# SCH_homework1_2025-05-14.net
KiCad netlist of a schematic drawn in EasyEDA
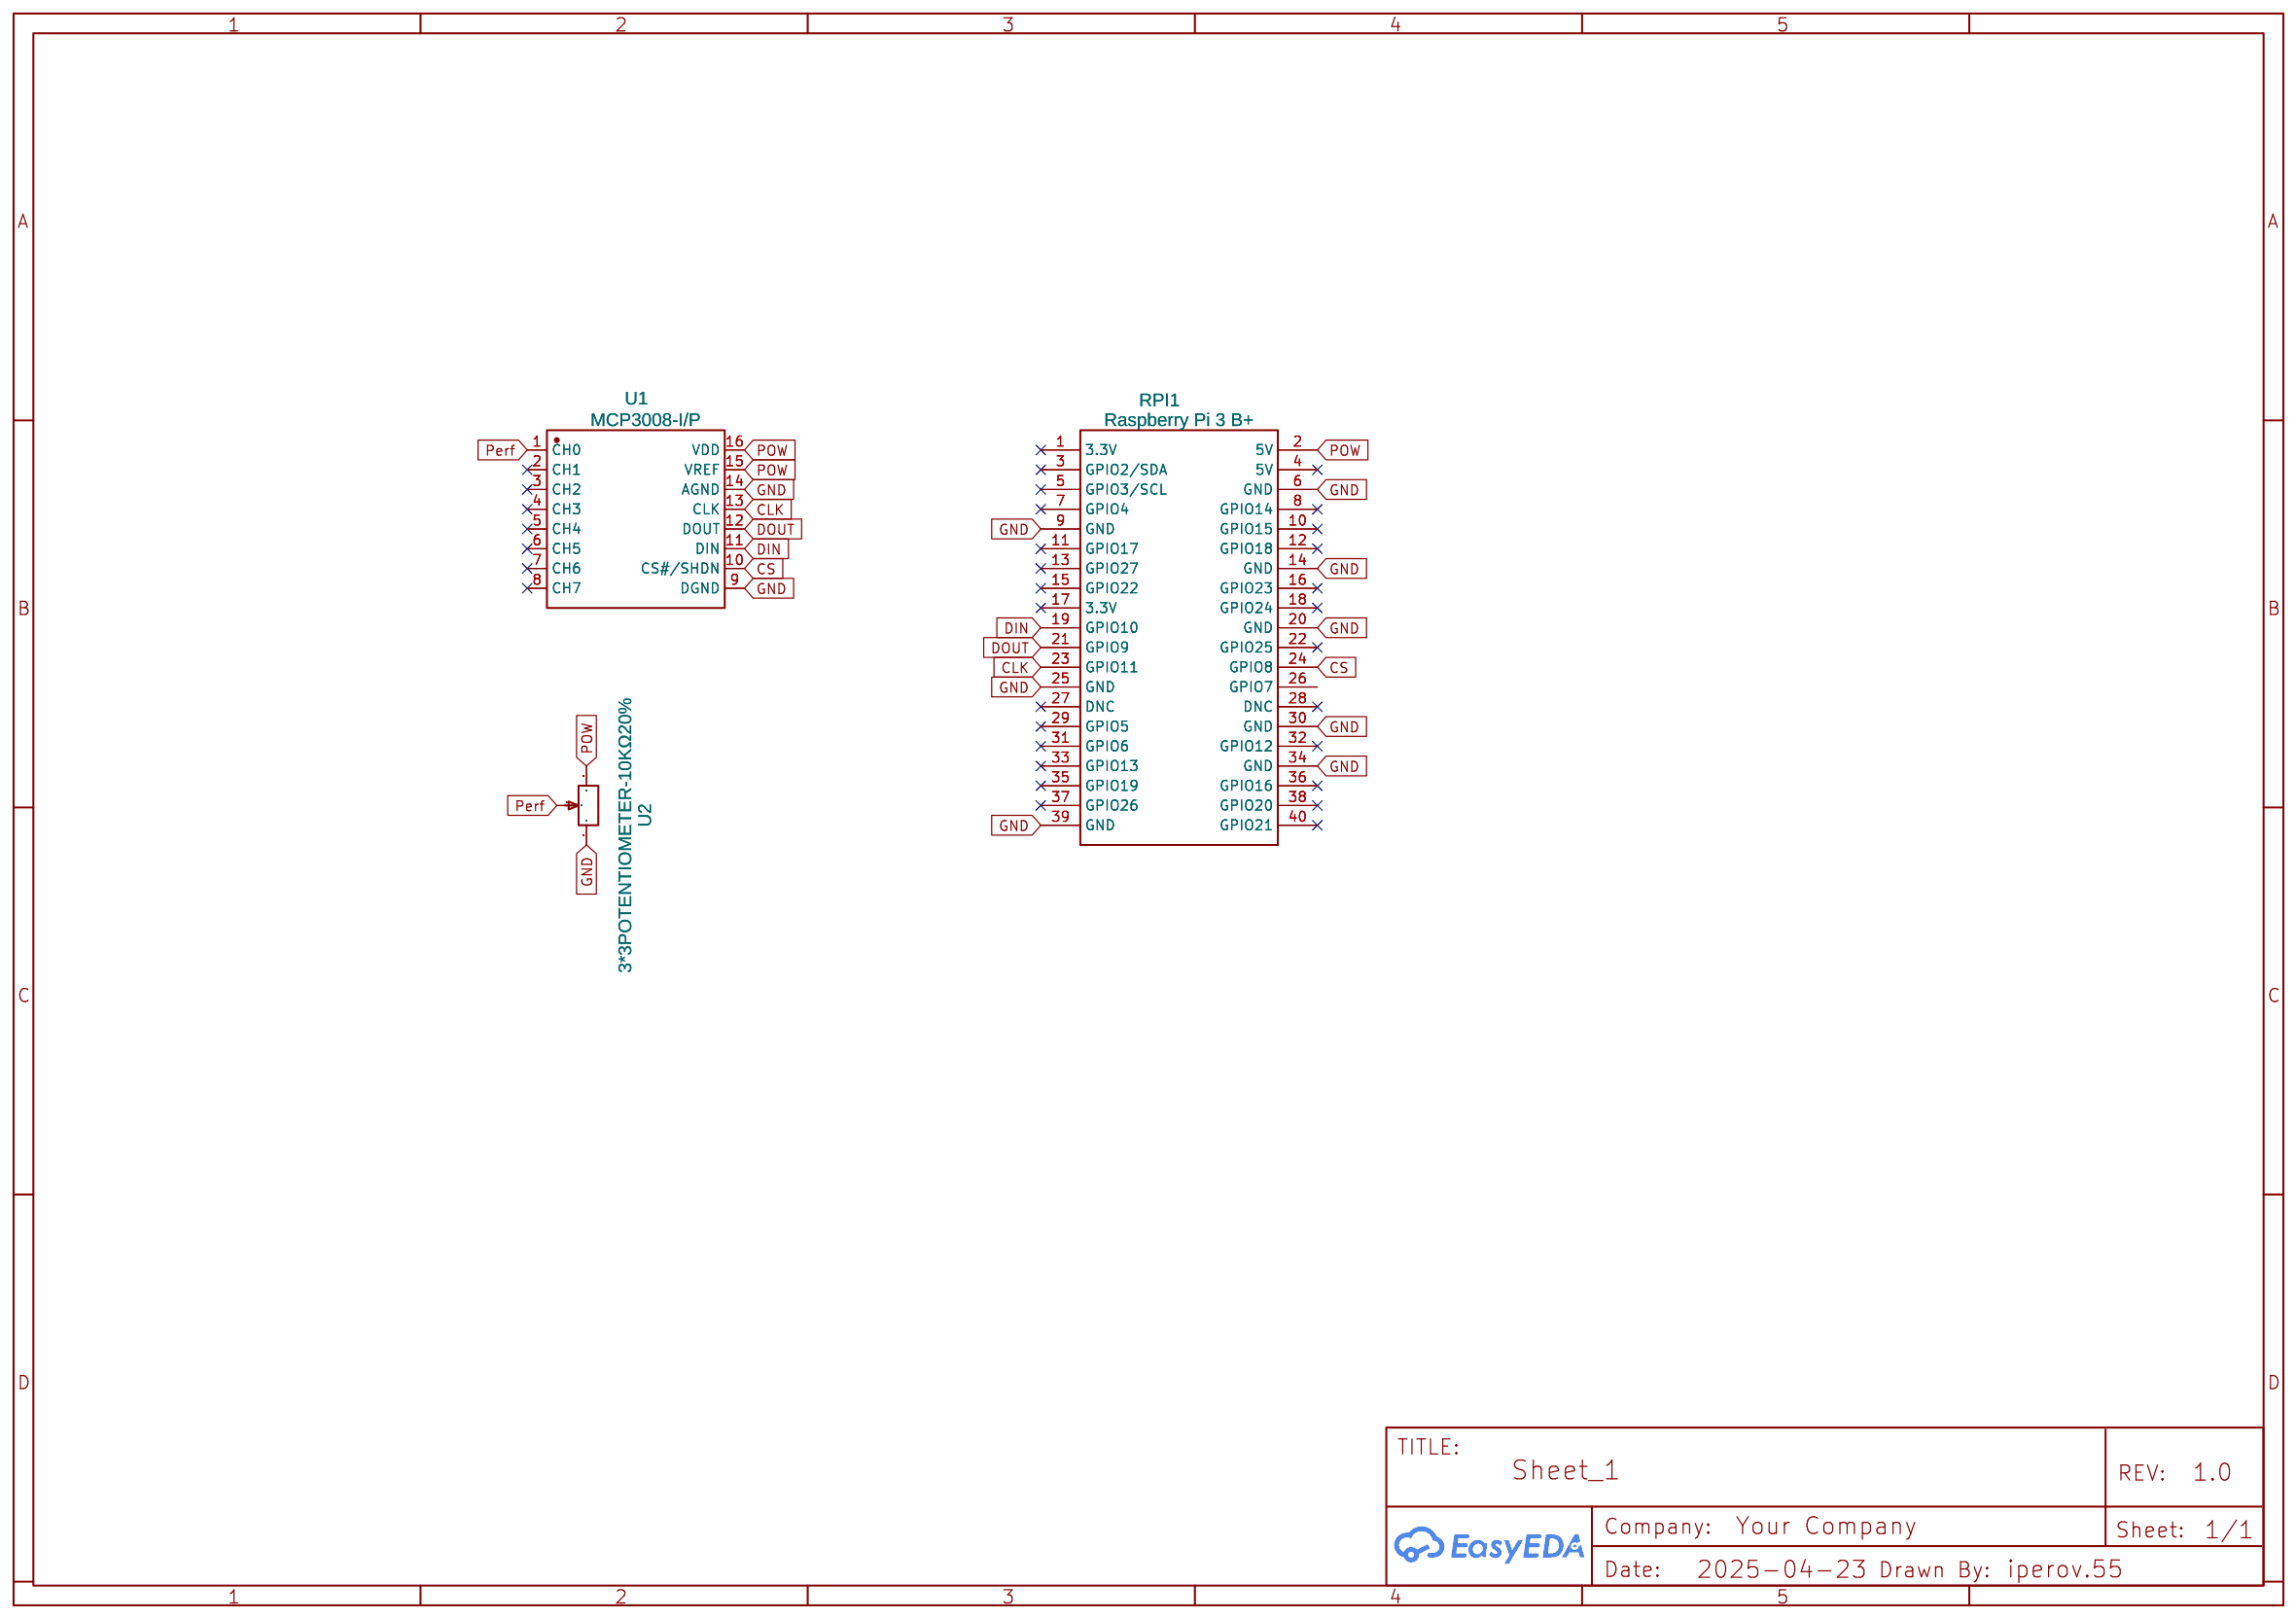
[diagram p0: schematic sheet]

(export (version "E")
  (design (tool "Eeschema 10.0.6"))
  (components
    (comp (ref "RPI1")
      (value "Raspberry Pi 3 B+")
      (fields
        (field (name "Manufacturer Part") "Raspberry Pi 3 - Model B+ - 1.4GHz Cortex-A53 with 1GB RAM")
        (field (name "Manufacturer") "Raspberry Pi")
      )
      (libsource (lib "") (part "Raspberry Pi 3 B+"))
    )
    (comp (ref "U1")
      (value "MCP3008-I/P")
      (fields (field (name "Manufacturer") "MICROCHIP(美国微芯)"))
      (libsource (lib "") (part "MCP3008-I/P"))
    )
    (comp (ref "U2")
      (value "3*3POTENTIOMETER-10KΩ20%")
      (fields (field (name "Manufacturer Part") "3*3Potentiometer-10kΩ20%"))
      (libsource (lib "") (part "3*3POTENTIOMETER-10KΩ20%"))
    )
  )
  (nets
    (net (code "1") (name "CLK") (class "Default")
      (node (ref "RPI1") (pin "23") (pinfunction "GPIO11_23") (pintype "bidirectional"))
      (node (ref "U1") (pin "13") (pinfunction "CLK_13") (pintype "unspecified"))
    )
    (net (code "2") (name "CS") (class "Default")
      (node (ref "RPI1") (pin "24") (pinfunction "GPIO8_24") (pintype "bidirectional"))
      (node (ref "U1") (pin "10") (pinfunction "CS#/SHDN_10") (pintype "unspecified"))
    )
    (net (code "3") (name "DIN") (class "Default")
      (node (ref "RPI1") (pin "19") (pinfunction "GPIO10_19") (pintype "bidirectional"))
      (node (ref "U1") (pin "11") (pinfunction "DIN_11") (pintype "unspecified"))
    )
    (net (code "4") (name "DOUT") (class "Default")
      (node (ref "RPI1") (pin "21") (pinfunction "GPIO9_21") (pintype "bidirectional"))
      (node (ref "U1") (pin "12") (pinfunction "DOUT_12") (pintype "unspecified"))
    )
    (net (code "5") (name "GND") (class "Default")
      (node (ref "RPI1") (pin "14") (pinfunction "GND_14") (pintype "unspecified"))
      (node (ref "RPI1") (pin "20") (pinfunction "GND_20") (pintype "unspecified"))
      (node (ref "RPI1") (pin "25") (pinfunction "GND_25") (pintype "unspecified"))
      (node (ref "RPI1") (pin "30") (pinfunction "GND_30") (pintype "unspecified"))
      (node (ref "RPI1") (pin "34") (pinfunction "GND_34") (pintype "unspecified"))
      (node (ref "RPI1") (pin "39") (pinfunction "GND_39") (pintype "unspecified"))
      (node (ref "RPI1") (pin "6") (pinfunction "GND_6") (pintype "unspecified"))
      (node (ref "RPI1") (pin "9") (pinfunction "GND_9") (pintype "unspecified"))
      (node (ref "U1") (pin "14") (pinfunction "AGND_14") (pintype "unspecified"))
      (node (ref "U1") (pin "9") (pinfunction "DGND_9") (pintype "unspecified"))
      (node (ref "U2") (pin "1") (pinfunction "1_1") (pintype "input"))
    )
    (net (code "6") (name "POW") (class "Default")
      (node (ref "RPI1") (pin "2") (pinfunction "5V_2") (pintype "passive"))
      (node (ref "U1") (pin "15") (pinfunction "VREF_15") (pintype "unspecified"))
      (node (ref "U1") (pin "16") (pinfunction "VDD_16") (pintype "unspecified"))
      (node (ref "U2") (pin "3") (pinfunction "3_3") (pintype "input"))
    )
    (net (code "7") (name "Perf") (class "Default")
      (node (ref "U1") (pin "1") (pinfunction "CH0_1") (pintype "unspecified"))
      (node (ref "U2") (pin "2") (pinfunction "2_2") (pintype "input"))
    )
    (net (code "8") (name "unconnected-(RPI1-3.3V-Pad1)") (class "Default")
      (node (ref "RPI1") (pin "1") (pinfunction "3.3V_1") (pintype "passive+no_connect"))
    )
    (net (code "9") (name "unconnected-(RPI1-3.3V-Pad17)") (class "Default")
      (node (ref "RPI1") (pin "17") (pinfunction "3.3V_17") (pintype "passive+no_connect"))
    )
    (net (code "10") (name "unconnected-(RPI1-5V-Pad4)") (class "Default")
      (node (ref "RPI1") (pin "4") (pinfunction "5V_4") (pintype "passive+no_connect"))
    )
    (net (code "11") (name "unconnected-(RPI1-DNC-Pad27)") (class "Default")
      (node (ref "RPI1") (pin "27") (pinfunction "DNC_27") (pintype "unspecified+no_connect"))
    )
    (net (code "12") (name "unconnected-(RPI1-DNC-Pad28)") (class "Default")
      (node (ref "RPI1") (pin "28") (pinfunction "DNC_28") (pintype "unspecified+no_connect"))
    )
    (net (code "13") (name "unconnected-(RPI1-GPIO2{slash}SDA-Pad3)") (class "Default")
      (node (ref "RPI1") (pin "3") (pinfunction "GPIO2/SDA_3") (pintype "bidirectional+no_connect"))
    )
    (net (code "14") (name "unconnected-(RPI1-GPIO3{slash}SCL-Pad5)") (class "Default")
      (node (ref "RPI1") (pin "5") (pinfunction "GPIO3/SCL_5") (pintype "bidirectional+no_connect"))
    )
    (net (code "15") (name "unconnected-(RPI1-GPIO4-Pad7)") (class "Default")
      (node (ref "RPI1") (pin "7") (pinfunction "GPIO4_7") (pintype "bidirectional+no_connect"))
    )
    (net (code "16") (name "unconnected-(RPI1-GPIO5-Pad29)") (class "Default")
      (node (ref "RPI1") (pin "29") (pinfunction "GPIO5_29") (pintype "bidirectional+no_connect"))
    )
    (net (code "17") (name "unconnected-(RPI1-GPIO6-Pad31)") (class "Default")
      (node (ref "RPI1") (pin "31") (pinfunction "GPIO6_31") (pintype "bidirectional+no_connect"))
    )
    (net (code "18") (name "unconnected-(RPI1-GPIO7-Pad26)") (class "Default")
      (node (ref "RPI1") (pin "26") (pinfunction "GPIO7_26") (pintype "bidirectional"))
    )
    (net (code "19") (name "unconnected-(RPI1-GPIO12-Pad32)") (class "Default")
      (node (ref "RPI1") (pin "32") (pinfunction "GPIO12_32") (pintype "bidirectional+no_connect"))
    )
    (net (code "20") (name "unconnected-(RPI1-GPIO13-Pad33)") (class "Default")
      (node (ref "RPI1") (pin "33") (pinfunction "GPIO13_33") (pintype "bidirectional+no_connect"))
    )
    (net (code "21") (name "unconnected-(RPI1-GPIO14-Pad8)") (class "Default")
      (node (ref "RPI1") (pin "8") (pinfunction "GPIO14_8") (pintype "bidirectional+no_connect"))
    )
    (net (code "22") (name "unconnected-(RPI1-GPIO15-Pad10)") (class "Default")
      (node (ref "RPI1") (pin "10") (pinfunction "GPIO15_10") (pintype "bidirectional+no_connect"))
    )
    (net (code "23") (name "unconnected-(RPI1-GPIO16-Pad36)") (class "Default")
      (node (ref "RPI1") (pin "36") (pinfunction "GPIO16_36") (pintype "bidirectional+no_connect"))
    )
    (net (code "24") (name "unconnected-(RPI1-GPIO17-Pad11)") (class "Default")
      (node (ref "RPI1") (pin "11") (pinfunction "GPIO17_11") (pintype "bidirectional+no_connect"))
    )
    (net (code "25") (name "unconnected-(RPI1-GPIO18-Pad12)") (class "Default")
      (node (ref "RPI1") (pin "12") (pinfunction "GPIO18_12") (pintype "bidirectional+no_connect"))
    )
    (net (code "26") (name "unconnected-(RPI1-GPIO19-Pad35)") (class "Default")
      (node (ref "RPI1") (pin "35") (pinfunction "GPIO19_35") (pintype "bidirectional+no_connect"))
    )
    (net (code "27") (name "unconnected-(RPI1-GPIO20-Pad38)") (class "Default")
      (node (ref "RPI1") (pin "38") (pinfunction "GPIO20_38") (pintype "bidirectional+no_connect"))
    )
    (net (code "28") (name "unconnected-(RPI1-GPIO21-Pad40)") (class "Default")
      (node (ref "RPI1") (pin "40") (pinfunction "GPIO21_40") (pintype "bidirectional+no_connect"))
    )
    (net (code "29") (name "unconnected-(RPI1-GPIO22-Pad15)") (class "Default")
      (node (ref "RPI1") (pin "15") (pinfunction "GPIO22_15") (pintype "bidirectional+no_connect"))
    )
    (net (code "30") (name "unconnected-(RPI1-GPIO23-Pad16)") (class "Default")
      (node (ref "RPI1") (pin "16") (pinfunction "GPIO23_16") (pintype "bidirectional+no_connect"))
    )
    (net (code "31") (name "unconnected-(RPI1-GPIO24-Pad18)") (class "Default")
      (node (ref "RPI1") (pin "18") (pinfunction "GPIO24_18") (pintype "bidirectional+no_connect"))
    )
    (net (code "32") (name "unconnected-(RPI1-GPIO25-Pad22)") (class "Default")
      (node (ref "RPI1") (pin "22") (pinfunction "GPIO25_22") (pintype "bidirectional+no_connect"))
    )
    (net (code "33") (name "unconnected-(RPI1-GPIO26-Pad37)") (class "Default")
      (node (ref "RPI1") (pin "37") (pinfunction "GPIO26_37") (pintype "bidirectional+no_connect"))
    )
    (net (code "34") (name "unconnected-(RPI1-GPIO27-Pad13)") (class "Default")
      (node (ref "RPI1") (pin "13") (pinfunction "GPIO27_13") (pintype "bidirectional+no_connect"))
    )
    (net (code "35") (name "unconnected-(U1-CH1-Pad2)") (class "Default")
      (node (ref "U1") (pin "2") (pinfunction "CH1_2") (pintype "unspecified+no_connect"))
    )
    (net (code "36") (name "unconnected-(U1-CH2-Pad3)") (class "Default")
      (node (ref "U1") (pin "3") (pinfunction "CH2_3") (pintype "unspecified+no_connect"))
    )
    (net (code "37") (name "unconnected-(U1-CH3-Pad4)") (class "Default")
      (node (ref "U1") (pin "4") (pinfunction "CH3_4") (pintype "unspecified+no_connect"))
    )
    (net (code "38") (name "unconnected-(U1-CH4-Pad5)") (class "Default")
      (node (ref "U1") (pin "5") (pinfunction "CH4_5") (pintype "unspecified+no_connect"))
    )
    (net (code "39") (name "unconnected-(U1-CH5-Pad6)") (class "Default")
      (node (ref "U1") (pin "6") (pinfunction "CH5_6") (pintype "unspecified+no_connect"))
    )
    (net (code "40") (name "unconnected-(U1-CH6-Pad7)") (class "Default")
      (node (ref "U1") (pin "7") (pinfunction "CH6_7") (pintype "unspecified+no_connect"))
    )
    (net (code "41") (name "unconnected-(U1-CH7-Pad8)") (class "Default")
      (node (ref "U1") (pin "8") (pinfunction "CH7_8") (pintype "unspecified+no_connect"))
    )
  )
)
